# power.net
KiCad netlist of a schematic drawn in Altium Designer
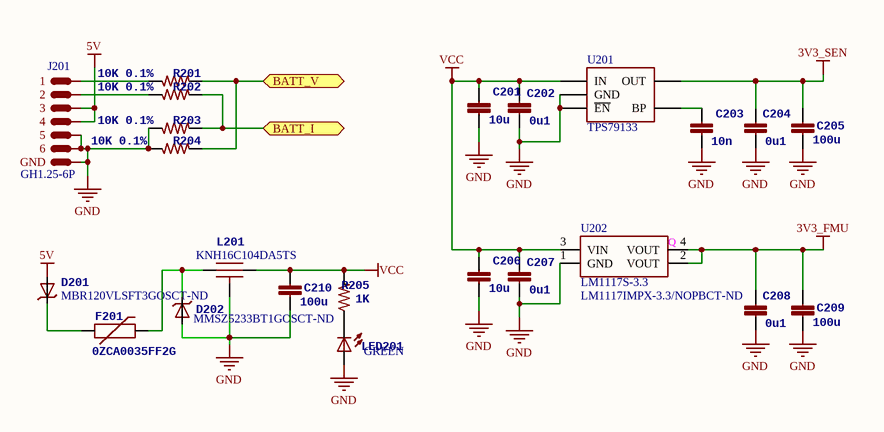
[diagram p0: power.SchDoc]

(export (version "E")
  (design (tool "Eeschema 10.0.6"))
  (components
    (comp (ref "C201")
      (value "10u")
      (footprint "0805-CAP")
      (description "Capacitor, 10uF, 10V, Y5V, 0805, Ceramic")
      (fields (field (name "PARTNO") "CC0805ZKY5V6BB106") (field (name "3DR_PARTNO") "ECM0713"))
      (libsource (lib "Q's无源元件类") (part "CAP0805-10uF"))
    )
    (comp (ref "C202")
      (value "0u1")
      (footprint "0603-CAP")
      (description "Capacitor, 0.1uF, 16V, Y5V, 0402, Ceramic")
      (fields (field (name "PARTNO") "CC0402ZRY5V7BB104") (field (name "3DR_PARTNO") "ECM0700"))
      (libsource (lib "Q's无源元件类") (part "CAP0603-0.1uF"))
    )
    (comp (ref "C203")
      (value "10n")
      (footprint "0603-CAP")
      (description "Capacitor, 10nF, 50V")
      (fields (field (name "PARTNO") "CC0402ZRY5V7BB104") (field (name "3DR_PARTNO") "ECM0700"))
      (libsource (lib "Q's无源元件类") (part "CAP0603-10nF"))
    )
    (comp (ref "C204")
      (value "0u1")
      (footprint "0603-CAP")
      (description "Capacitor, 0.1uF, 16V, Y5V, 0402, Ceramic")
      (fields (field (name "PARTNO") "CC0402ZRY5V7BB104") (field (name "3DR_PARTNO") "ECM0700"))
      (libsource (lib "Q's无源元件类") (part "CAP0603-0.1uF"))
    )
    (comp (ref "C205")
      (value "100u")
      (footprint "1206-CAP")
      (description "CAP CER 100UF 10V 20% X5R 1206")
      (fields (field (name "PARTNO") "C3216X5R1A107M160AC") (field (name "3DR_PARTNO") "ECM0716"))
      (libsource (lib "Q's无源元件类") (part "CAP1206-100uF"))
    )
    (comp (ref "C206")
      (value "10u")
      (footprint "0805-CAP")
      (description "Capacitor, 10uF, 10V, Y5V, 0805, Ceramic")
      (fields (field (name "PARTNO") "CC0805ZKY5V6BB106") (field (name "3DR_PARTNO") "ECM0713"))
      (libsource (lib "Q's无源元件类") (part "CAP0805-10uF"))
    )
    (comp (ref "C207")
      (value "0u1")
      (footprint "0603-CAP")
      (description "Capacitor, 0.1uF, 16V, Y5V, 0402, Ceramic")
      (fields (field (name "PARTNO") "CC0402ZRY5V7BB104") (field (name "3DR_PARTNO") "ECM0700"))
      (libsource (lib "Q's无源元件类") (part "CAP0603-0.1uF"))
    )
    (comp (ref "C208")
      (value "0u1")
      (footprint "0603-CAP")
      (description "Capacitor, 0.1uF, 16V, Y5V, 0402, Ceramic")
      (fields (field (name "PARTNO") "CC0402ZRY5V7BB104") (field (name "3DR_PARTNO") "ECM0700"))
      (libsource (lib "Q's无源元件类") (part "CAP0603-0.1uF"))
    )
    (comp (ref "C209")
      (value "100u")
      (footprint "1206-CAP")
      (description "CAP CER 100UF 10V 20% X5R 1206")
      (fields (field (name "PARTNO") "C3216X5R1A107M160AC") (field (name "3DR_PARTNO") "ECM0716"))
      (libsource (lib "Q's无源元件类") (part "CAP1206-100uF"))
    )
    (comp (ref "C210")
      (value "100u")
      (footprint "1206-CAP")
      (description "CAP CER 100UF 10V 20% X5R 1206")
      (fields (field (name "PARTNO") "C3216X5R1A107M160AC") (field (name "3DR_PARTNO") "ECM0716"))
      (libsource (lib "Q's无源元件类") (part "CAP1206-100uF"))
    )
    (comp (ref "D201")
      (value "MBR120VLSFT3GOSCT")
      (footprint "SOD-123LF")
      (description "DIODE SCHOTTKY 20V 1A , 0.34V, SOD123FL")
      (fields (field (name "SUPPLIER PART NUMBER 1") "MBR120VLSFT3GOSCT-ND"))
      (libsource (lib "Q's无源元件类") (part "DIODE-SBD_SOD123FL"))
    )
    (comp (ref "D202")
      (value "MMSZ5233BT1G")
      (footprint "SOD-123LF")
      (description "DIODE ZENER 6V 500MW SOD123")
      (fields (field (name "SUPPLIER PART NUMBER 1") "MMSZ5233BT1GOSCT-ND"))
      (libsource (lib "Q's无源元件类") (part "DIODE-ZENER"))
    )
    (comp (ref "F201")
      (value "0ZCA0035FF2G")
      (footprint "1206-FUSE")
      (description "PTC RESTTBLE 0.35A 16V CHIP 1206, 自恢复保险")
      (fields (field (name "3DR_PARTNO") "ECM0802"))
      (libsource (lib "Q's无源元件类") (part "FUSE-1206"))
    )
    (comp (ref "J201")
      (value "GH1.25-6P")
      (footprint "1.25-6P")
      (description "GH1.25mm 立贴 间距1.25mm 连接器贴片")
      (libsource (lib "Q's端子及图标") (part "GH1.25-6P"))
    )
    (comp (ref "L201")
      (value "KNH16C104DA5TS")
      (footprint "0603-KNH16-DA")
      (description "EMI FILTER CAP 0.1UF 2A 25V 0603")
      (fields (field (name "3DR_PARTNO") "ECM0719") (field (name "PARTNO") "KNH16C104DA5TS"))
      (libsource (lib "Q's无源元件类") (part "EMI Filters"))
    )
    (comp (ref "LED201")
      (value "APG1608CGKC")
      (footprint "0603-LED")
      (description "2.1v, LED GREEN CLEAR 0603 SMD")
      (fields (field (name "3DR_PARTNO") "ECM0515") (field (name "COLOR") "GREEN"))
      (libsource (lib "Q's无源元件类") (part "LED0603-GREEN"))
    )
    (comp (ref "R201")
      (value "10K 0.1%")
      (footprint "0603-RES")
      (description "RES 10 OHM 1/10W 0.1% 0603")
      (libsource (lib "Q's无源元件类") (part "RES0603-10k_0.1%"))
    )
    (comp (ref "R202")
      (value "10K 0.1%")
      (footprint "0603-RES")
      (description "RES 10 OHM 1/10W 0.1% 0603")
      (libsource (lib "Q's无源元件类") (part "RES0603-10k_0.1%"))
    )
    (comp (ref "R203")
      (value "10K 0.1%")
      (footprint "0603-RES")
      (description "RES 10 OHM 1/10W 0.1% 0603")
      (libsource (lib "Q's无源元件类") (part "RES0603-10k_0.1%"))
    )
    (comp (ref "R204")
      (value "10K 0.1%")
      (footprint "0603-RES")
      (description "RES 10 OHM 1/10W 0.1% 0603")
      (libsource (lib "Q's无源元件类") (part "RES0603-10k_0.1%"))
    )
    (comp (ref "R205")
      (value "1K")
      (footprint "0603-RES")
      (description "RES 1K OHM 1/10W 5% 0603")
      (libsource (lib "Q's无源元件类") (part "RES0603-1K"))
    )
    (comp (ref "U201")
      (value "TPS79133")
      (footprint "R-PDSO-G5")
      (libsource (lib "Q's有源芯片类") (part "LDO-TPS79133"))
    )
    (comp (ref "U202")
      (value "LM1117S-3.3")
      (footprint "Q's有源芯片类:SOT223-4N")
      (description "LDO, ouput 3.3V/1A, 0.04% Line Regulation and 0.1% load Regulation.")
      (fields (field (name "SUPPLIER PART NUMBER 1") "LM1117IMPX-3.3/NOPBCT-ND"))
      (libsource (lib "Q's有源芯片类") (part "LDO-LM1117S-3.3"))
    )
  )
  (nets
    (net (code "1") (name "/BATT_I") (class "Default")
      (node (ref "R202") (pin "2") (pinfunction "2_2") (pintype "passive"))
      (node (ref "R203") (pin "2") (pinfunction "2_2") (pintype "passive"))
    )
    (net (code "2") (name "/BATT_V") (class "Default")
      (node (ref "R201") (pin "2") (pinfunction "2_2") (pintype "passive"))
      (node (ref "R204") (pin "2") (pinfunction "2_2") (pintype "passive"))
    )
    (net (code "3") (name "3V3_FMU") (class "Default")
      (node (ref "C208") (pin "P$1") (pinfunction "1_P$1") (pintype "passive"))
      (node (ref "C209") (pin "P$1") (pinfunction "1_P$1") (pintype "passive"))
      (node (ref "U202") (pin "2") (pinfunction "VOUT_2") (pintype "passive"))
      (node (ref "U202") (pin "4") (pinfunction "VOUT_4") (pintype "passive"))
    )
    (net (code "4") (name "3V3_SEN") (class "Default")
      (node (ref "C204") (pin "P$1") (pinfunction "1_P$1") (pintype "passive"))
      (node (ref "C205") (pin "P$1") (pinfunction "1_P$1") (pintype "passive"))
      (node (ref "U201") (pin "5") (pinfunction "OUT_5") (pintype "passive"))
    )
    (net (code "5") (name "5V") (class "Default")
      (node (ref "D201") (pin "A") (pinfunction "A_A") (pintype "passive"))
      (node (ref "J201") (pin "3") (pinfunction "3_3") (pintype "passive"))
      (node (ref "J201") (pin "4") (pinfunction "4_4") (pintype "passive"))
    )
    (net (code "6") (name "GND") (class "Default")
      (node (ref "C201") (pin "P$2") (pinfunction "2_P$2") (pintype "passive"))
      (node (ref "C202") (pin "P$2") (pinfunction "2_P$2") (pintype "passive"))
      (node (ref "C203") (pin "P$2") (pinfunction "2_P$2") (pintype "passive"))
      (node (ref "C204") (pin "P$2") (pinfunction "2_P$2") (pintype "passive"))
      (node (ref "C205") (pin "P$2") (pinfunction "2_P$2") (pintype "passive"))
      (node (ref "C206") (pin "P$2") (pinfunction "2_P$2") (pintype "passive"))
      (node (ref "C207") (pin "P$2") (pinfunction "2_P$2") (pintype "passive"))
      (node (ref "C208") (pin "P$2") (pinfunction "2_P$2") (pintype "passive"))
      (node (ref "C209") (pin "P$2") (pinfunction "2_P$2") (pintype "passive"))
      (node (ref "C210") (pin "P$2") (pinfunction "2_P$2") (pintype "passive"))
      (node (ref "D202") (pin "A") (pinfunction "A_A") (pintype "passive"))
      (node (ref "J201") (pin "5") (pinfunction "5_5") (pintype "passive"))
      (node (ref "J201") (pin "6") (pinfunction "6_6") (pintype "passive"))
      (node (ref "J201") (pin "GND") (pinfunction "GND_GND") (pintype "passive"))
      (node (ref "L201") (pin "GND") (pinfunction "GND_GND") (pintype "passive"))
      (node (ref "LED201") (pin "A") (pinfunction "A_A") (pintype "passive"))
      (node (ref "R203") (pin "1") (pinfunction "1_1") (pintype "passive"))
      (node (ref "R204") (pin "1") (pinfunction "1_1") (pintype "passive"))
      (node (ref "U201") (pin "2") (pinfunction "GND_2") (pintype "passive"))
      (node (ref "U201") (pin "3") (pinfunction "~{EN}_3") (pintype "passive"))
      (node (ref "U202") (pin "1") (pinfunction "GND_1") (pintype "passive"))
    )
    (net (code "7") (name "Net-(C203-1)") (class "Default")
      (node (ref "C203") (pin "P$1") (pinfunction "1_P$1") (pintype "passive"))
      (node (ref "U201") (pin "4") (pinfunction "BP_4") (pintype "passive"))
    )
    (net (code "8") (name "Net-(D201-PadC)") (class "Default")
      (node (ref "D201") (pin "C") (pinfunction "C_C") (pintype "passive"))
      (node (ref "F201") (pin "1") (pinfunction "1_1") (pintype "passive"))
    )
    (net (code "9") (name "Net-(D202-PadC)") (class "Default")
      (node (ref "D202") (pin "C") (pinfunction "C_C") (pintype "passive"))
      (node (ref "F201") (pin "2") (pinfunction "2_2") (pintype "passive"))
      (node (ref "L201") (pin "P$1") (pinfunction "P$1_P$1") (pintype "passive"))
    )
    (net (code "10") (name "Net-(J201-Pad1)") (class "Default")
      (node (ref "J201") (pin "1") (pinfunction "1_1") (pintype "passive"))
      (node (ref "R201") (pin "1") (pinfunction "1_1") (pintype "passive"))
    )
    (net (code "11") (name "Net-(J201-Pad2)") (class "Default")
      (node (ref "J201") (pin "2") (pinfunction "2_2") (pintype "passive"))
      (node (ref "R202") (pin "1") (pinfunction "1_1") (pintype "passive"))
    )
    (net (code "12") (name "Net-(LED201-PadC)") (class "Default")
      (node (ref "LED201") (pin "C") (pinfunction "C_C") (pintype "passive"))
      (node (ref "R205") (pin "1") (pinfunction "1_1") (pintype "passive"))
    )
    (net (code "13") (name "VCC") (class "Default")
      (node (ref "C201") (pin "P$1") (pinfunction "1_P$1") (pintype "passive"))
      (node (ref "C202") (pin "P$1") (pinfunction "1_P$1") (pintype "passive"))
      (node (ref "C206") (pin "P$1") (pinfunction "1_P$1") (pintype "passive"))
      (node (ref "C207") (pin "P$1") (pinfunction "1_P$1") (pintype "passive"))
      (node (ref "C210") (pin "P$1") (pinfunction "1_P$1") (pintype "passive"))
      (node (ref "L201") (pin "P$2") (pinfunction "P$2_P$2") (pintype "passive"))
      (node (ref "R205") (pin "2") (pinfunction "2_2") (pintype "passive"))
      (node (ref "U201") (pin "1") (pinfunction "IN_1") (pintype "passive"))
      (node (ref "U202") (pin "3") (pinfunction "VIN_3") (pintype "passive"))
    )
  )
)
